# MCU_STM32F4.net
KiCad netlist of a schematic drawn in Altium Designer
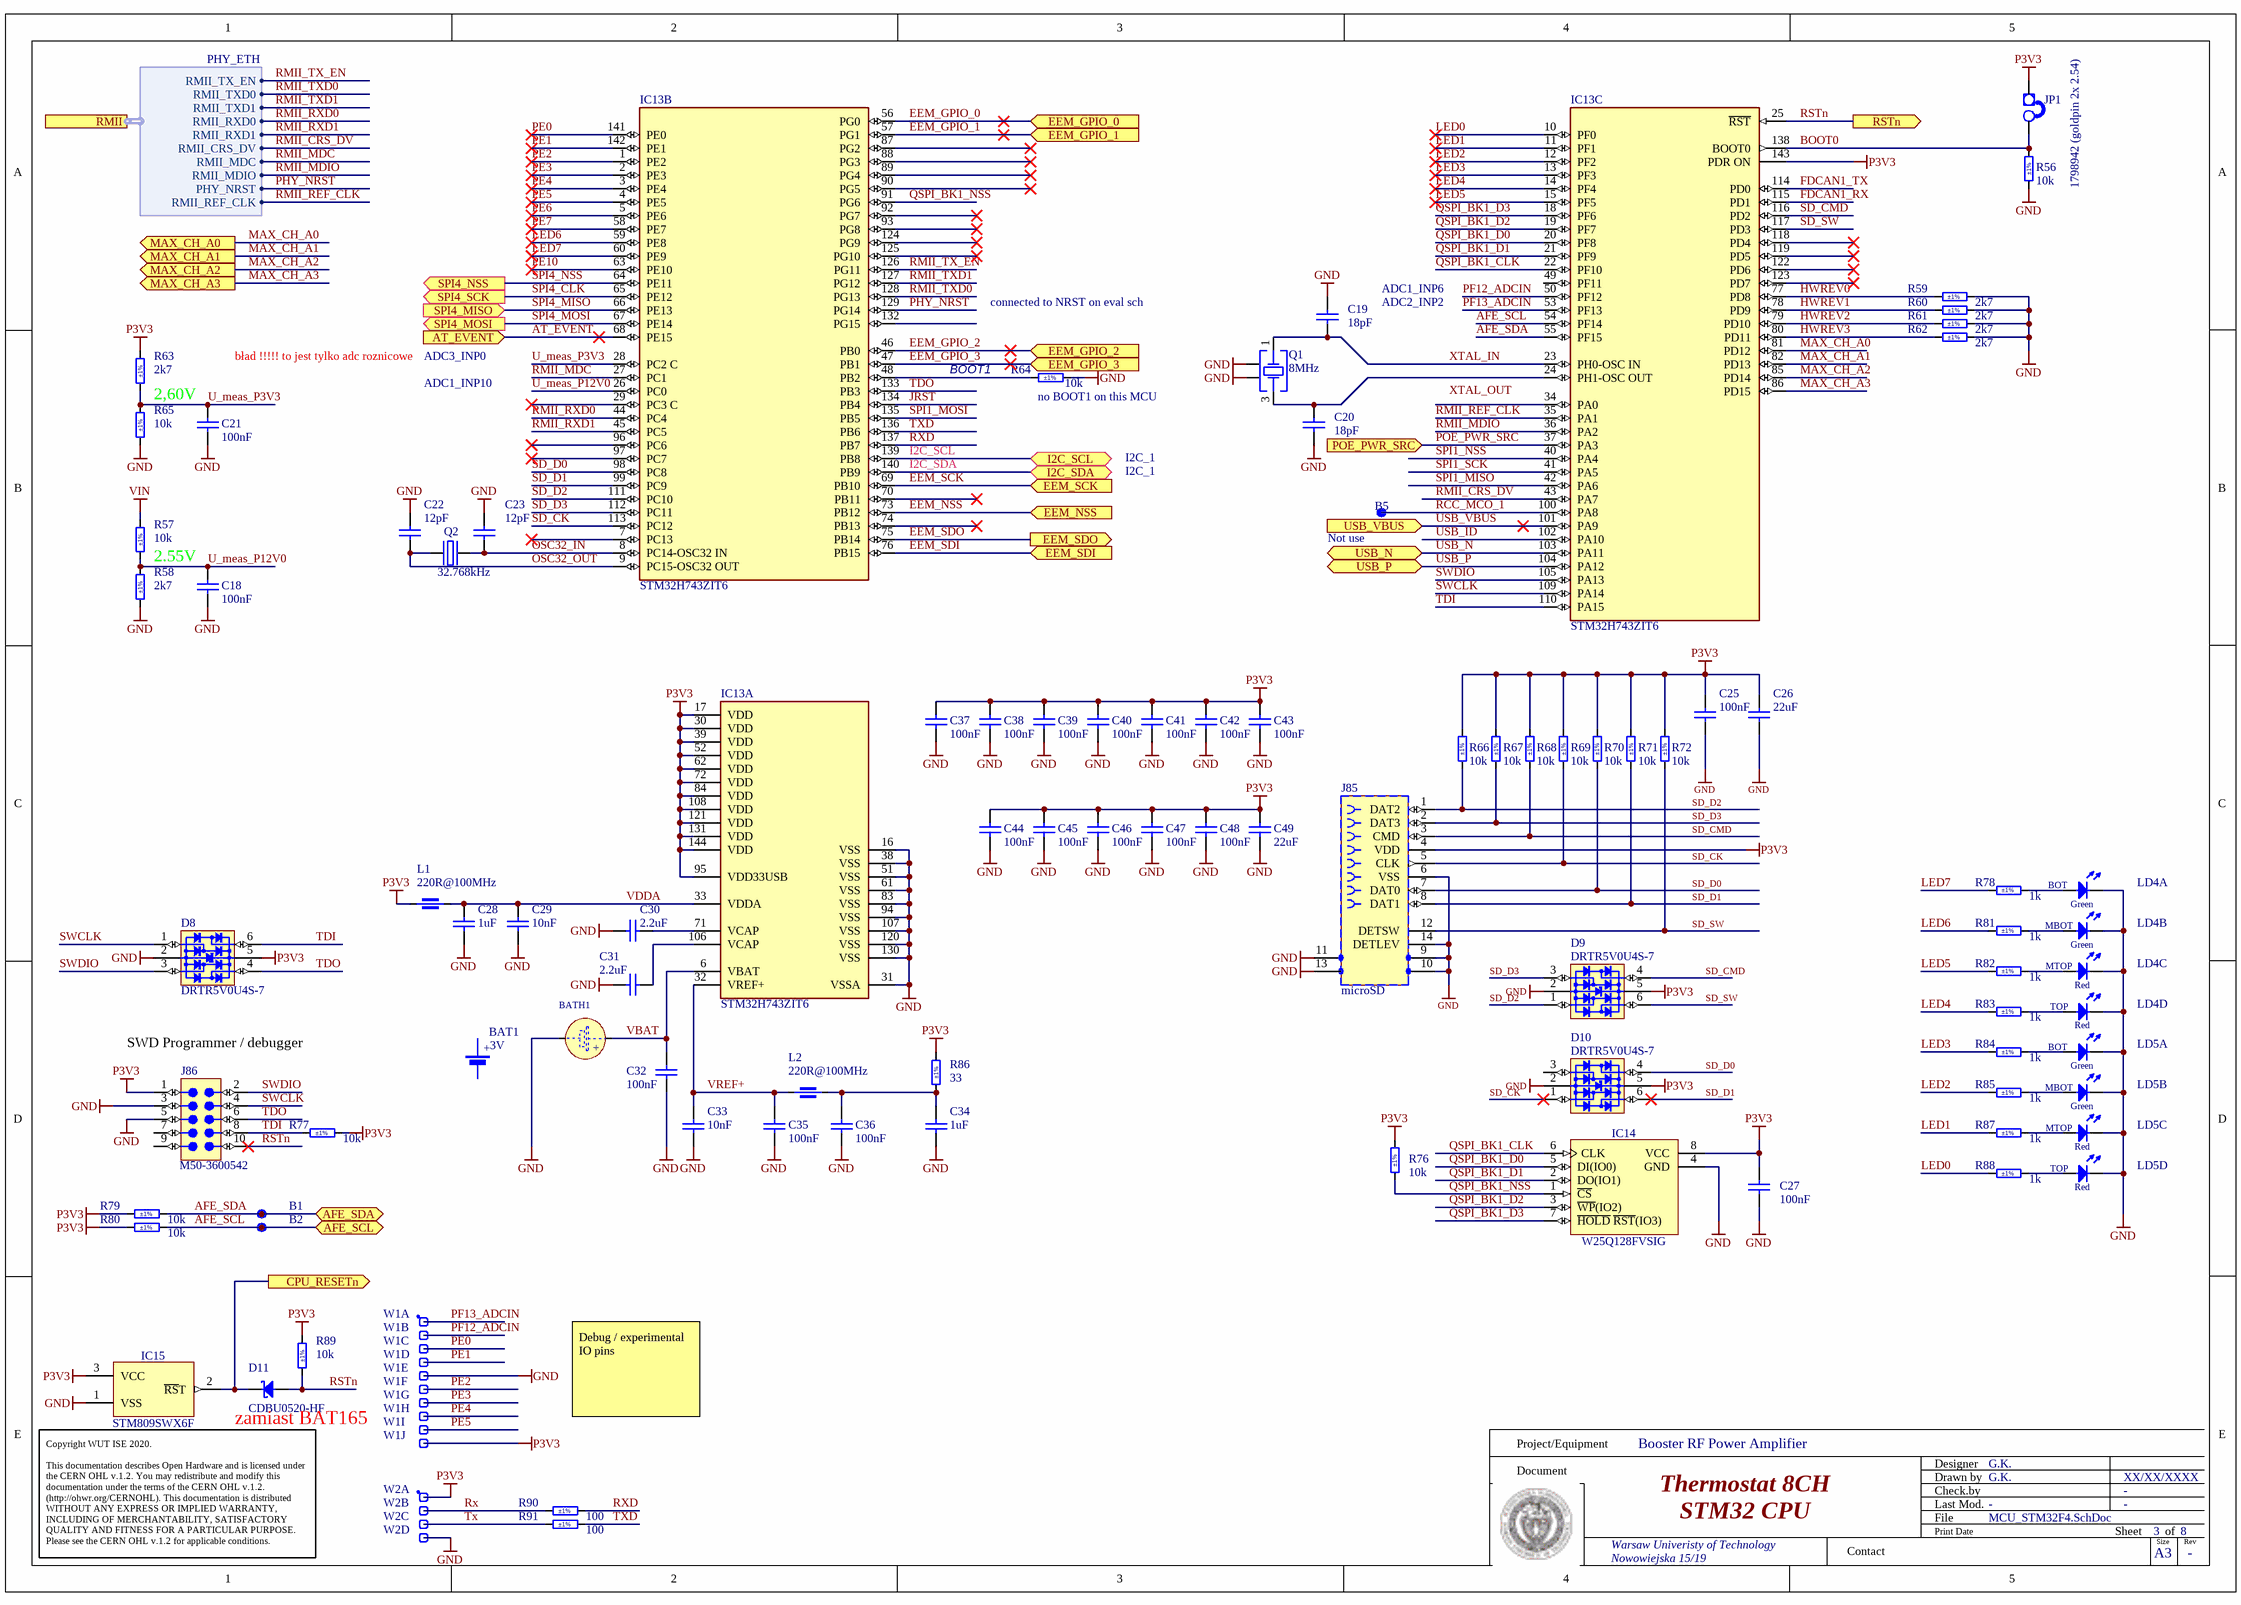
[diagram p0: MCU_STM32F4.SchDoc]

(export (version "E")
  (design (tool "Eeschema 10.0.6"))
  (components
    (comp (ref "B1")
      (value "SMD Pad")
      (footprint "C100")
      (description "Pad")
      (fields (field (name "PART NUMBER") "SMD_PAD_D1MM") (field (name "AUTHOR") "CERN DEM JLC"))
      (libsource (lib "Eletro-mechanical") (part "Single SMD Pad (Round)"))
    )
    (comp (ref "B2")
      (value "SMD Pad")
      (footprint "C100")
      (description "Pad")
      (fields (field (name "PART NUMBER") "SMD_PAD_D1MM") (field (name "AUTHOR") "CERN DEM JLC"))
      (libsource (lib "Eletro-mechanical") (part "Single SMD Pad (Round)"))
    )
    (comp (ref "B5")
      (value "SMD Pad")
      (footprint "C100")
      (description "Through Hole Pad")
      (fields (field (name "PART NUMBER") "SMD_PAD_D1MM") (field (name "AUTHOR") "CERN DEM JLC"))
      (libsource (lib "Eletro-mechanical") (part "Single SMD Pad (Round)"))
    )
    (comp (ref "BAT1")
      (value "3V")
      (footprint "BAT_VARTA_CR1220")
      (description "Battery for use only with Socket Holder")
      (fields
        (field (name "PART NUMBER") "BAT_VARTA_CR1220")
        (field (name "POWER") "35mAh")
        (field (name "AUTHOR") "CERN DEM JLC")
      )
      (libsource (lib "Eletro-mechanical") (part "Battery No Pin"))
    )
    (comp (ref "BATH1")
      (value "~")
      (footprint "BATH_KEYSTONE_3000")
      (description "Battery Holder whit 2 Pin")
      (fields
        (field (name "PART NUMBER") "BATH_KEYSTONE_3000")
        (field (name "MANUFACTURER") "KEYSTONE")
        (field (name "AUTHOR") "CERN DEM JLC")
      )
      (libsource (lib "Eletro-mechanical") (part "Battery Holder 2 Pin"))
    )
    (comp (ref "C18")
      (value "100nF")
      (footprint "CAPC1608X87N")
      (description "Non-polarised capacitor")
      (fields
        (field (name "PART NUMBER") "CC0603_100NF_50V_10%_X7R")
        (field (name "VOLTAGE") "50V")
        (field (name "AUTHOR") "CERN DEM JLC")
      )
      (libsource (lib "Capacitors") (part "Capacitor - non polarized"))
    )
    (comp (ref "C19")
      (value "18pF")
      (footprint "CAPC1608X87N")
      (description "Non-polarised capacitor")
      (fields
        (field (name "PART NUMBER") "CC0603_18PF_50V_5%_NP0")
        (field (name "VOLTAGE") "50V")
        (field (name "AUTHOR") "CERN DEM JLC")
      )
      (libsource (lib "Capacitors") (part "Capacitor - non polarized"))
    )
    (comp (ref "C20")
      (value "18pF")
      (footprint "CAPC1608X87N")
      (description "Non-polarised capacitor")
      (fields
        (field (name "PART NUMBER") "CC0603_18PF_50V_5%_NP0")
        (field (name "VOLTAGE") "50V")
        (field (name "AUTHOR") "CERN DEM JLC")
      )
      (libsource (lib "Capacitors") (part "Capacitor - non polarized"))
    )
    (comp (ref "C21")
      (value "100nF")
      (footprint "CAPC1608X87N")
      (description "Non-polarised capacitor")
      (fields
        (field (name "PART NUMBER") "CC0603_100NF_50V_10%_X7R")
        (field (name "VOLTAGE") "50V")
        (field (name "AUTHOR") "CERN DEM JLC")
      )
      (libsource (lib "Capacitors") (part "Capacitor - non polarized"))
    )
    (comp (ref "C22")
      (value "12pF")
      (footprint "CAPC1608X87N")
      (description "Non-polarised capacitor")
      (fields
        (field (name "PART NUMBER") "CC0603_12PF_50V_5%_NP0")
        (field (name "VOLTAGE") "50V")
        (field (name "AUTHOR") "CERN DEM JLC")
      )
      (libsource (lib "Capacitors") (part "Capacitor - non polarized"))
    )
    (comp (ref "C23")
      (value "12pF")
      (footprint "CAPC1608X87N")
      (description "Non-polarised capacitor")
      (fields
        (field (name "PART NUMBER") "CC0603_12PF_50V_5%_NP0")
        (field (name "VOLTAGE") "50V")
        (field (name "AUTHOR") "CERN DEM JLC")
      )
      (libsource (lib "Capacitors") (part "Capacitor - non polarized"))
    )
    (comp (ref "C25")
      (value "100nF")
      (footprint "CAPC1608X87N")
      (description "Non-polarised capacitor")
      (fields
        (field (name "PART NUMBER") "CC0603_100NF_50V_10%_X7R")
        (field (name "VOLTAGE") "50V")
        (field (name "AUTHOR") "CERN DEM JLC")
      )
      (libsource (lib "Capacitors") (part "Capacitor - non polarized"))
    )
    (comp (ref "C26")
      (value "22uF")
      (footprint "CAPC2012X135N")
      (description "Non-polarised capacitor")
      (fields
        (field (name "PART NUMBER") "CC0805_22UF_16V_10%_X5R")
        (field (name "VOLTAGE") "16V")
        (field (name "AUTHOR") "CERN DEM JLC")
      )
      (libsource (lib "Capacitors") (part "Capacitor - non polarized"))
    )
    (comp (ref "C27")
      (value "100nF")
      (footprint "CAPC1608X87N")
      (description "Non-polarised capacitor")
      (fields
        (field (name "PART NUMBER") "CC0603_100NF_50V_10%_X7R")
        (field (name "VOLTAGE") "50V")
        (field (name "AUTHOR") "CERN DEM JLC")
      )
      (libsource (lib "Capacitors") (part "Capacitor - non polarized"))
    )
    (comp (ref "C28")
      (value "1uF")
      (footprint "CAPC1608X87N")
      (description "Non-polarised capacitor")
      (fields
        (field (name "PART NUMBER") "CC0603_1UF_16V_10%_X7R")
        (field (name "VOLTAGE") "16V")
        (field (name "AUTHOR") "CERN DEM JLC")
      )
      (libsource (lib "Capacitors") (part "Capacitor - non polarized"))
    )
    (comp (ref "C29")
      (value "10nF")
      (footprint "CAPC1608X87N")
      (description "Non-polarised capacitor")
      (fields
        (field (name "PART NUMBER") "CC0603_10NF_50V_10%_X7R")
        (field (name "VOLTAGE") "50V")
        (field (name "AUTHOR") "CERN DEM JLC")
      )
      (libsource (lib "Capacitors") (part "Capacitor - non polarized"))
    )
    (comp (ref "C30")
      (value "2.2uF")
      (footprint "CAPC1608X90N")
      (description "Non-polarised capacitor")
      (fields
        (field (name "PART NUMBER") "CC0603_2.2UF_10V_20%_X7R")
        (field (name "VOLTAGE") "10V")
        (field (name "AUTHOR") "CERN DEM JLC")
      )
      (libsource (lib "Capacitors") (part "Capacitor - non polarized"))
    )
    (comp (ref "C31")
      (value "2.2uF")
      (footprint "CAPC1608X90N")
      (description "Non-polarised capacitor")
      (fields
        (field (name "PART NUMBER") "CC0603_2.2UF_10V_20%_X7R")
        (field (name "VOLTAGE") "10V")
        (field (name "AUTHOR") "CERN DEM JLC")
      )
      (libsource (lib "Capacitors") (part "Capacitor - non polarized"))
    )
    (comp (ref "C32")
      (value "100nF")
      (footprint "CAPC1608X87N")
      (description "Non-polarised capacitor")
      (fields
        (field (name "PART NUMBER") "CC0603_100NF_50V_10%_X7R")
        (field (name "VOLTAGE") "50V")
        (field (name "AUTHOR") "CERN DEM JLC")
      )
      (libsource (lib "Capacitors") (part "Capacitor - non polarized"))
    )
    (comp (ref "C33")
      (value "10nF")
      (footprint "CAPC1608X87N")
      (description "Non-polarised capacitor")
      (fields
        (field (name "PART NUMBER") "CC0603_10NF_50V_10%_X7R")
        (field (name "VOLTAGE") "50V")
        (field (name "AUTHOR") "CERN DEM JLC")
      )
      (libsource (lib "Capacitors") (part "Capacitor - non polarized"))
    )
    (comp (ref "C34")
      (value "1uF")
      (footprint "CAPC1608X87N")
      (description "Non-polarised capacitor")
      (fields
        (field (name "PART NUMBER") "CC0603_1UF_16V_10%_X7R")
        (field (name "VOLTAGE") "16V")
        (field (name "AUTHOR") "CERN DEM JLC")
      )
      (libsource (lib "Capacitors") (part "Capacitor - non polarized"))
    )
    (comp (ref "C35")
      (value "100nF")
      (footprint "CAPC1608X87N")
      (description "Non-polarised capacitor")
      (fields
        (field (name "PART NUMBER") "CC0603_100NF_50V_10%_X7R")
        (field (name "VOLTAGE") "50V")
        (field (name "AUTHOR") "CERN DEM JLC")
      )
      (libsource (lib "Capacitors") (part "Capacitor - non polarized"))
    )
    (comp (ref "C36")
      (value "100nF")
      (footprint "CAPC1608X87N")
      (description "Non-polarised capacitor")
      (fields
        (field (name "PART NUMBER") "CC0603_100NF_50V_10%_X7R")
        (field (name "VOLTAGE") "50V")
        (field (name "AUTHOR") "CERN DEM JLC")
      )
      (libsource (lib "Capacitors") (part "Capacitor - non polarized"))
    )
    (comp (ref "C37")
      (value "100nF")
      (footprint "CAPC1608X87N")
      (description "Non-polarised capacitor")
      (fields
        (field (name "PART NUMBER") "CC0603_100NF_50V_10%_X7R")
        (field (name "VOLTAGE") "50V")
        (field (name "AUTHOR") "CERN DEM JLC")
      )
      (libsource (lib "Capacitors") (part "Capacitor - non polarized"))
    )
    (comp (ref "C38")
      (value "100nF")
      (footprint "CAPC1608X87N")
      (description "Non-polarised capacitor")
      (fields
        (field (name "PART NUMBER") "CC0603_100NF_50V_10%_X7R")
        (field (name "VOLTAGE") "50V")
        (field (name "AUTHOR") "CERN DEM JLC")
      )
      (libsource (lib "Capacitors") (part "Capacitor - non polarized"))
    )
    (comp (ref "C39")
      (value "100nF")
      (footprint "CAPC1608X87N")
      (description "Non-polarised capacitor")
      (fields
        (field (name "PART NUMBER") "CC0603_100NF_50V_10%_X7R")
        (field (name "VOLTAGE") "50V")
        (field (name "AUTHOR") "CERN DEM JLC")
      )
      (libsource (lib "Capacitors") (part "Capacitor - non polarized"))
    )
    (comp (ref "C40")
      (value "100nF")
      (footprint "CAPC1608X87N")
      (description "Non-polarised capacitor")
      (fields
        (field (name "PART NUMBER") "CC0603_100NF_50V_10%_X7R")
        (field (name "VOLTAGE") "50V")
        (field (name "AUTHOR") "CERN DEM JLC")
      )
      (libsource (lib "Capacitors") (part "Capacitor - non polarized"))
    )
    (comp (ref "C41")
      (value "100nF")
      (footprint "CAPC1608X87N")
      (description "Non-polarised capacitor")
      (fields
        (field (name "PART NUMBER") "CC0603_100NF_50V_10%_X7R")
        (field (name "VOLTAGE") "50V")
        (field (name "AUTHOR") "CERN DEM JLC")
      )
      (libsource (lib "Capacitors") (part "Capacitor - non polarized"))
    )
    (comp (ref "C42")
      (value "100nF")
      (footprint "CAPC1608X87N")
      (description "Non-polarised capacitor")
      (fields
        (field (name "PART NUMBER") "CC0603_100NF_50V_10%_X7R")
        (field (name "VOLTAGE") "50V")
        (field (name "AUTHOR") "CERN DEM JLC")
      )
      (libsource (lib "Capacitors") (part "Capacitor - non polarized"))
    )
    (comp (ref "C43")
      (value "100nF")
      (footprint "CAPC1608X87N")
      (description "Non-polarised capacitor")
      (fields
        (field (name "PART NUMBER") "CC0603_100NF_50V_10%_X7R")
        (field (name "VOLTAGE") "50V")
        (field (name "AUTHOR") "CERN DEM JLC")
      )
      (libsource (lib "Capacitors") (part "Capacitor - non polarized"))
    )
    (comp (ref "C44")
      (value "100nF")
      (footprint "CAPC1608X87N")
      (description "Non-polarised capacitor")
      (fields
        (field (name "PART NUMBER") "CC0603_100NF_50V_10%_X7R")
        (field (name "VOLTAGE") "50V")
        (field (name "AUTHOR") "CERN DEM JLC")
      )
      (libsource (lib "Capacitors") (part "Capacitor - non polarized"))
    )
    (comp (ref "C45")
      (value "100nF")
      (footprint "CAPC1608X87N")
      (description "Non-polarised capacitor")
      (fields
        (field (name "PART NUMBER") "CC0603_100NF_50V_10%_X7R")
        (field (name "VOLTAGE") "50V")
        (field (name "AUTHOR") "CERN DEM JLC")
      )
      (libsource (lib "Capacitors") (part "Capacitor - non polarized"))
    )
    (comp (ref "C46")
      (value "100nF")
      (footprint "CAPC1608X87N")
      (description "Non-polarised capacitor")
      (fields
        (field (name "PART NUMBER") "CC0603_100NF_50V_10%_X7R")
        (field (name "VOLTAGE") "50V")
        (field (name "AUTHOR") "CERN DEM JLC")
      )
      (libsource (lib "Capacitors") (part "Capacitor - non polarized"))
    )
    (comp (ref "C47")
      (value "100nF")
      (footprint "CAPC1608X87N")
      (description "Non-polarised capacitor")
      (fields
        (field (name "PART NUMBER") "CC0603_100NF_50V_10%_X7R")
        (field (name "VOLTAGE") "50V")
        (field (name "AUTHOR") "CERN DEM JLC")
      )
      (libsource (lib "Capacitors") (part "Capacitor - non polarized"))
    )
    (comp (ref "C48")
      (value "100nF")
      (footprint "CAPC1608X87N")
      (description "Non-polarised capacitor")
      (fields
        (field (name "PART NUMBER") "CC0603_100NF_50V_10%_X7R")
        (field (name "VOLTAGE") "50V")
        (field (name "AUTHOR") "CERN DEM JLC")
      )
      (libsource (lib "Capacitors") (part "Capacitor - non polarized"))
    )
    (comp (ref "C49")
      (value "22uF")
      (footprint "CAPC2012X135N")
      (description "Non-polarised capacitor")
      (fields
        (field (name "PART NUMBER") "CC0805_22UF_16V_10%_X5R")
        (field (name "VOLTAGE") "16V")
        (field (name "AUTHOR") "CERN DEM JLC")
      )
      (libsource (lib "Capacitors") (part "Capacitor - non polarized"))
    )
    (comp (ref "D8")
      (value "DRTR5V0U4S-7")
      (footprint "SOT65P210X110-6N")
      (description "Integrated Quad Ultra-Low Capacitance ESD Protection")
      (fields (field (name "MANUFACTURER") "DIODES") (field (name "AUTHOR") "GK"))
      (libsource (lib "Diodes") (part "D_TVS_DRTR5V0U4S-7"))
    )
    (comp (ref "D9")
      (value "DRTR5V0U4S-7")
      (footprint "SOT65P210X110-6N")
      (description "Integrated Quad Ultra-Low Capacitance ESD Protection")
      (fields (field (name "MANUFACTURER") "DIODES") (field (name "AUTHOR") "GK"))
      (libsource (lib "Diodes") (part "D_TVS_DRTR5V0U4S-7"))
    )
    (comp (ref "D10")
      (value "DRTR5V0U4S-7")
      (footprint "SOT65P210X110-6N")
      (description "Integrated Quad Ultra-Low Capacitance ESD Protection")
      (fields (field (name "MANUFACTURER") "DIODES") (field (name "AUTHOR") "GK"))
      (libsource (lib "Diodes") (part "D_TVS_DRTR5V0U4S-7"))
    )
    (comp (ref "D11")
      (value "CDBU0520-HF")
      (footprint "SOD-523F")
      (description "Schottky Diode")
      (fields
        (field (name "VOLTAGE") "20V")
        (field (name "POWER") "500mA")
        (field (name "AUTHOR") "CERN DEM HF")
      )
      (libsource (lib "ICs And Semiconductors") (part "Diode Schottky"))
    )
    (comp (ref "IC13")
      (value "STM32H743ZIT6")
      (footprint "FP-LQFP144-1A-MFG")
      (description "IC MCU 32BIT 2MB FLASH 144LQFP")
      (fields
        (field (name "MANUFACTURER") "STMicroelectronics")
        (field (name "OCTOPART") "https://octopart.com/stm32h743zit6-stmicroelectronics-76372529")
      )
      (libsource (lib "Altium Content Vault") (part "4977c5c7f8d170b58ef15f889e64ba1"))
    )
    (comp (ref "IC14")
      (value "W25Q128FVSIG")
      (footprint "SOIC127P790X216-8N")
      (description "128M-bit Serial Flash Memory with uniform 4KB sectors and Dual/Quad SPI and QPI")
      (fields (field (name "MANUFACTURER") "WINBOND") (field (name "AUTHOR") "CERN DEM MR"))
      (libsource (lib "ICs And Semiconductors") (part "W25Q128FVSIG"))
    )
    (comp (ref "IC15")
      (value "STM809SWX6F")
      (footprint "SOT95P237X112-3N")
      (description "3-Pin Microprocessor Reset Circuit")
      (fields (field (name "MANUFACTURER") "ST MICROELECTRONICS") (field (name "AUTHOR") "CERN DEM JMW"))
      (libsource (lib "ICs And Semiconductors") (part "STM809SWX6F"))
    )
    (comp (ref "J85")
      (value "microSD")
      (footprint "MOLEX_502570-0893")
      (description "Connector MicroSD 8 Pin")
      (fields
        (field (name "PART NUMBER") "MOLEX_502570-0893")
        (field (name "MANUFACTURER") "MOLEX")
        (field (name "AUTHOR") "CERN DEM JLC")
      )
      (libsource (lib "Connectors") (part "MOLEX_502570-0893"))
    )
    (comp (ref "J86")
      (value "Header 10")
      (footprint "HARWIN_M50-3600542")
      (description "10 Contacts - Pitch 1.27mm - Dual Row SMT Vertical Pin Header (Post Lead = 3mm, Insulator 1mm)")
      (fields
        (field (name "PART NUMBER") "HARWIN_M50-3600542")
        (field (name "MANUFACTURER") "HARWIN")
        (field (name "MANUFACTURER PART NUMBER") "M50-3600542")
        (field (name "AUTHOR") "GK")
      )
      (libsource (lib "PT1000_16CH") (part "CON_2x10 1.27 SMT_male_HARWIN"))
    )
    (comp (ref "JP1")
      (value "1798942 (goldpin 2x 2.54)")
      (footprint "jump")
      (description "Jumper")
      (libsource (lib "PT1000_16CH") (part "JUMPER"))
    )
    (comp (ref "L1")
      (value "220R@100MHz")
      (footprint "INDC1608X95N")
      (fields
        (field (name "PART NUMBER") "IND0603_MURATA_BLM18SG221TN1")
        (field (name "POWER") "2.5A")
        (field (name "TOLERANCE") "±25%")
        (field (name "AUTHOR") "CERN DEM MR")
      )
      (libsource (lib "Inductors & Transformers") (part "Ferrite Bead"))
    )
    (comp (ref "L2")
      (value "220R@100MHz")
      (footprint "INDC1608X95N")
      (fields
        (field (name "PART NUMBER") "IND0603_MURATA_BLM18SG221TN1")
        (field (name "POWER") "2.5A")
        (field (name "TOLERANCE") "±25%")
        (field (name "AUTHOR") "CERN DEM MR")
      )
      (libsource (lib "Inductors & Transformers") (part "Ferrite Bead"))
    )
    (comp (ref "LD4")
      (value "Green/Green/HeRed/HeRed")
      (footprint "LED_BIVAR_H485CHHGGDL")
      (description "LED x4 G-1C2A-BOT_G-3C4A_H-5C6A_H-7C8A-TOP")
      (fields
        (field (name "PART NUMBER") "LED_BIVAR_H485CHHGGDL")
        (field (name "MANUFACTURER") "BIVAR")
        (field (name "AUTHOR") "CERN DEM BC")
      )
      (libsource (lib "ICs And Semiconductors") (part "LED x4 G-1C2A-BOT_G-3C4A_H-5C6A_H-7C8A-TOP"))
    )
    (comp (ref "LD5")
      (value "Green/Green/HeRed/HeRed")
      (footprint "LED_BIVAR_H485CHHGGDL")
      (description "LED x4 G-1C2A-BOT_G-3C4A_H-5C6A_H-7C8A-TOP")
      (fields
        (field (name "PART NUMBER") "LED_BIVAR_H485CHHGGDL")
        (field (name "MANUFACTURER") "BIVAR")
        (field (name "AUTHOR") "CERN DEM BC")
      )
      (libsource (lib "ICs And Semiconductors") (part "LED x4 G-1C2A-BOT_G-3C4A_H-5C6A_H-7C8A-TOP"))
    )
    (comp (ref "Q1")
      (value "8MHz")
      (footprint "WE-XTAL_CFPX-180")
      (description "WE-XTAL Quartz Crystal, SMT, CFPX-180, 8MHz, +/-30ppm")
      (fields
        (field (name "MANUFACTURER PART NUMBER") "830108313809")
        (field (name "MANUFACTURER") "Wurth Elektronik")
        (field (name "FREQUENCY") "8MHz")
      )
      (libsource (lib "Altium_WE-XTAL (rev22a)") (part "830108313809"))
    )
    (comp (ref "Q2")
      (value "32.768kHz")
      (footprint "XTAL_ABRACON_ABS06")
      (description "Quartz Crystal")
      (fields
        (field (name "PART NUMBER") "XTAL_32.768KHZ_ABRACON_ABS06-32.768KHZ-9")
        (field (name "MANUFACTURER") "ABRACON")
        (field (name "AUTHOR") "CERN DEM JMW")
      )
      (libsource (lib "ICs And Semiconductors") (part "Quartz Crystal"))
    )
    (comp (ref "R56")
      (value "10k")
      (footprint "RESC1608X55N")
      (description "Resistor - 1%")
      (fields
        (field (name "TOLERANCE") "±1%")
        (field (name "PART NUMBER") "R0603_10K_1%_0.1W_100PPM")
        (field (name "POWER") "0.1W")
        (field (name "AUTHOR") "CERN DEM JLC")
      )
      (libsource (lib "Resistors") (part "Resistor - 1%"))
    )
    (comp (ref "R57")
      (value "10k")
      (footprint "RESC1608X55N")
      (description "Resistor - 1%")
      (fields
        (field (name "TOLERANCE") "±1%")
        (field (name "PART NUMBER") "R0603_10K_1%_0.1W_100PPM")
        (field (name "POWER") "0.1W")
        (field (name "AUTHOR") "CERN DEM JLC")
      )
      (libsource (lib "Resistors") (part "Resistor - 1%"))
    )
    (comp (ref "R58")
      (value "2k7")
      (footprint "RESC1608X55N")
      (description "Resistor - 1%")
      (fields
        (field (name "TOLERANCE") "±1%")
        (field (name "PART NUMBER") "R0603_2K7_1%_0.1W_100PPM")
        (field (name "POWER") "0.1W")
        (field (name "AUTHOR") "CERN DEM JLC")
      )
      (libsource (lib "Resistors") (part "Resistor - 1%"))
    )
    (comp (ref "R59")
      (value "2k7")
      (footprint "RESC1608X55N")
      (description "Resistor - 1%")
      (fields
        (field (name "TOLERANCE") "±1%")
        (field (name "PART NUMBER") "R0603_2K7_1%_0.1W_100PPM")
        (field (name "POWER") "0.1W")
        (field (name "AUTHOR") "CERN DEM JLC")
      )
      (libsource (lib "Resistors") (part "Resistor - 1%"))
    )
    (comp (ref "R60")
      (value "2k7")
      (footprint "RESC1608X55N")
      (description "Resistor - 1%")
      (fields
        (field (name "TOLERANCE") "±1%")
        (field (name "PART NUMBER") "R0603_2K7_1%_0.1W_100PPM")
        (field (name "POWER") "0.1W")
        (field (name "AUTHOR") "CERN DEM JLC")
      )
      (libsource (lib "Resistors") (part "Resistor - 1%"))
    )
    (comp (ref "R61")
      (value "2k7")
      (footprint "RESC1608X55N")
      (description "Resistor - 1%")
      (fields
        (field (name "TOLERANCE") "±1%")
        (field (name "PART NUMBER") "R0603_2K7_1%_0.1W_100PPM")
        (field (name "POWER") "0.1W")
        (field (name "AUTHOR") "CERN DEM JLC")
      )
      (libsource (lib "Resistors") (part "Resistor - 1%"))
    )
    (comp (ref "R62")
      (value "2k7")
      (footprint "RESC1608X55N")
      (description "Resistor - 1%")
      (fields
        (field (name "TOLERANCE") "±1%")
        (field (name "PART NUMBER") "R0603_2K7_1%_0.1W_100PPM")
        (field (name "POWER") "0.1W")
        (field (name "AUTHOR") "CERN DEM JLC")
      )
      (libsource (lib "Resistors") (part "Resistor - 1%"))
    )
    (comp (ref "R63")
      (value "2k7")
      (footprint "RESC1608X55N")
      (description "Resistor - 1%")
      (fields
        (field (name "TOLERANCE") "±1%")
        (field (name "PART NUMBER") "R0603_2K7_1%_0.1W_100PPM")
        (field (name "POWER") "0.1W")
        (field (name "AUTHOR") "CERN DEM JLC")
      )
      (libsource (lib "Resistors") (part "Resistor - 1%"))
    )
    (comp (ref "R64")
      (value "10k")
      (footprint "RESC1608X55N")
      (description "Resistor - 1%")
      (fields
        (field (name "TOLERANCE") "±1%")
        (field (name "PART NUMBER") "R0603_10K_1%_0.1W_100PPM")
        (field (name "POWER") "0.1W")
        (field (name "AUTHOR") "CERN DEM JLC")
      )
      (libsource (lib "Resistors") (part "Resistor - 1%"))
    )
    (comp (ref "R65")
      (value "10k")
      (footprint "RESC1608X55N")
      (description "Resistor - 1%")
      (fields
        (field (name "TOLERANCE") "±1%")
        (field (name "PART NUMBER") "R0603_10K_1%_0.1W_100PPM")
        (field (name "POWER") "0.1W")
        (field (name "AUTHOR") "CERN DEM JLC")
      )
      (libsource (lib "Resistors") (part "Resistor - 1%"))
    )
    (comp (ref "R66")
      (value "10k")
      (footprint "RESC1608X55N")
      (description "Resistor - 1%")
      (fields
        (field (name "TOLERANCE") "±1%")
        (field (name "PART NUMBER") "R0603_10K_1%_0.1W_100PPM")
        (field (name "POWER") "0.1W")
        (field (name "AUTHOR") "CERN DEM JLC")
      )
      (libsource (lib "Resistors") (part "Resistor - 1%"))
    )
    (comp (ref "R67")
      (value "10k")
      (footprint "RESC1608X55N")
      (description "Resistor - 1%")
      (fields
        (field (name "TOLERANCE") "±1%")
        (field (name "PART NUMBER") "R0603_10K_1%_0.1W_100PPM")
        (field (name "POWER") "0.1W")
        (field (name "AUTHOR") "CERN DEM JLC")
      )
      (libsource (lib "Resistors") (part "Resistor - 1%"))
    )
    (comp (ref "R68")
      (value "10k")
      (footprint "RESC1608X55N")
      (description "Resistor - 1%")
      (fields
        (field (name "TOLERANCE") "±1%")
        (field (name "PART NUMBER") "R0603_10K_1%_0.1W_100PPM")
        (field (name "POWER") "0.1W")
        (field (name "AUTHOR") "CERN DEM JLC")
      )
      (libsource (lib "Resistors") (part "Resistor - 1%"))
    )
    (comp (ref "R69")
      (value "10k")
      (footprint "RESC1608X55N")
      (description "Resistor - 1%")
      (fields
        (field (name "TOLERANCE") "±1%")
        (field (name "PART NUMBER") "R0603_10K_1%_0.1W_100PPM")
        (field (name "POWER") "0.1W")
        (field (name "AUTHOR") "CERN DEM JLC")
      )
      (libsource (lib "Resistors") (part "Resistor - 1%"))
    )
    (comp (ref "R70")
      (value "10k")
      (footprint "RESC1608X55N")
      (description "Resistor - 1%")
      (fields
        (field (name "TOLERANCE") "±1%")
        (field (name "PART NUMBER") "R0603_10K_1%_0.1W_100PPM")
        (field (name "POWER") "0.1W")
        (field (name "AUTHOR") "CERN DEM JLC")
      )
      (libsource (lib "Resistors") (part "Resistor - 1%"))
    )
    (comp (ref "R71")
      (value "10k")
      (footprint "RESC1608X55N")
      (description "Resistor - 1%")
      (fields
        (field (name "TOLERANCE") "±1%")
        (field (name "PART NUMBER") "R0603_10K_1%_0.1W_100PPM")
        (field (name "POWER") "0.1W")
        (field (name "AUTHOR") "CERN DEM JLC")
      )
      (libsource (lib "Resistors") (part "Resistor - 1%"))
    )
    (comp (ref "R72")
      (value "10k")
      (footprint "RESC1608X55N")
      (description "Resistor - 1%")
      (fields
        (field (name "TOLERANCE") "±1%")
        (field (name "PART NUMBER") "R0603_10K_1%_0.1W_100PPM")
        (field (name "POWER") "0.1W")
        (field (name "AUTHOR") "CERN DEM JLC")
      )
      (libsource (lib "Resistors") (part "Resistor - 1%"))
    )
    (comp (ref "R76")
      (value "10k")
      (footprint "RESC1608X55N")
      (description "Resistor - 1%")
      (fields
        (field (name "TOLERANCE") "±1%")
        (field (name "PART NUMBER") "R0603_10K_1%_0.1W_100PPM")
        (field (name "POWER") "0.1W")
        (field (name "AUTHOR") "CERN DEM JLC")
      )
      (libsource (lib "Resistors") (part "Resistor - 1%"))
    )
    (comp (ref "R77")
      (value "10k")
      (footprint "RESC1608X55N")
      (description "Resistor - 1%")
      (fields
        (field (name "TOLERANCE") "±1%")
        (field (name "PART NUMBER") "R0603_10K_1%_0.1W_100PPM")
        (field (name "POWER") "0.1W")
        (field (name "AUTHOR") "CERN DEM JLC")
      )
      (libsource (lib "Resistors") (part "Resistor - 1%"))
    )
    (comp (ref "R78")
      (value "1k")
      (footprint "RESC1608X55N")
      (description "Resistor - 1%")
      (fields
        (field (name "TOLERANCE") "±1%")
        (field (name "PART NUMBER") "R0603_1K_1%_0.1W_100PPM")
        (field (name "POWER") "0.1W")
        (field (name "AUTHOR") "CERN DEM JLC")
      )
      (libsource (lib "Resistors") (part "Resistor - 1%"))
    )
    (comp (ref "R79")
      (value "10k")
      (footprint "RESC1608X55N")
      (description "Resistor - 1%")
      (fields
        (field (name "TOLERANCE") "±1%")
        (field (name "PART NUMBER") "R0603_10K_1%_0.1W_100PPM")
        (field (name "POWER") "0.1W")
        (field (name "AUTHOR") "CERN DEM JLC")
      )
      (libsource (lib "Resistors") (part "Resistor - 1%"))
    )
    (comp (ref "R80")
      (value "10k")
      (footprint "RESC1608X55N")
      (description "Resistor - 1%")
      (fields
        (field (name "TOLERANCE") "±1%")
        (field (name "PART NUMBER") "R0603_10K_1%_0.1W_100PPM")
        (field (name "POWER") "0.1W")
        (field (name "AUTHOR") "CERN DEM JLC")
      )
      (libsource (lib "Resistors") (part "Resistor - 1%"))
    )
    (comp (ref "R81")
      (value "1k")
      (footprint "RESC1608X55N")
      (description "Resistor - 1%")
      (fields
        (field (name "TOLERANCE") "±1%")
        (field (name "PART NUMBER") "R0603_1K_1%_0.1W_100PPM")
        (field (name "POWER") "0.1W")
        (field (name "AUTHOR") "CERN DEM JLC")
      )
      (libsource (lib "Resistors") (part "Resistor - 1%"))
    )
    (comp (ref "R82")
      (value "1k")
      (footprint "RESC1608X55N")
      (description "Resistor - 1%")
      (fields
        (field (name "TOLERANCE") "±1%")
        (field (name "PART NUMBER") "R0603_1K_1%_0.1W_100PPM")
        (field (name "POWER") "0.1W")
        (field (name "AUTHOR") "CERN DEM JLC")
      )
      (libsource (lib "Resistors") (part "Resistor - 1%"))
    )
    (comp (ref "R83")
      (value "1k")
      (footprint "RESC1608X55N")
      (description "Resistor - 1%")
      (fields
        (field (name "TOLERANCE") "±1%")
        (field (name "PART NUMBER") "R0603_1K_1%_0.1W_100PPM")
        (field (name "POWER") "0.1W")
        (field (name "AUTHOR") "CERN DEM JLC")
      )
      (libsource (lib "Resistors") (part "Resistor - 1%"))
    )
    (comp (ref "R84")
      (value "1k")
      (footprint "RESC1608X55N")
      (description "Resistor - 1%")
      (fields
        (field (name "TOLERANCE") "±1%")
        (field (name "PART NUMBER") "R0603_1K_1%_0.1W_100PPM")
        (field (name "POWER") "0.1W")
        (field (name "AUTHOR") "CERN DEM JLC")
      )
      (libsource (lib "Resistors") (part "Resistor - 1%"))
    )
    (comp (ref "R85")
      (value "1k")
      (footprint "RESC1608X55N")
      (description "Resistor - 1%")
      (fields
        (field (name "TOLERANCE") "±1%")
        (field (name "PART NUMBER") "R0603_1K_1%_0.1W_100PPM")
        (field (name "POWER") "0.1W")
        (field (name "AUTHOR") "CERN DEM JLC")
      )
      (libsource (lib "Resistors") (part "Resistor - 1%"))
    )
    (comp (ref "R86")
      (value "33")
      (footprint "RESC1608X55N")
      (description "Resistor - 1%")
      (fields
        (field (name "TOLERANCE") "±1%")
        (field (name "PART NUMBER") "R0603_33R_1%_0.1W_100PPM")
        (field (name "POWER") "0.1W")
        (field (name "AUTHOR") "CERN DEM JLC")
      )
      (libsource (lib "Resistors") (part "Resistor - 1%"))
    )
    (comp (ref "R87")
      (value "1k")
      (footprint "RESC1608X55N")
      (description "Resistor - 1%")
      (fields
        (field (name "TOLERANCE") "±1%")
        (field (name "PART NUMBER") "R0603_1K_1%_0.1W_100PPM")
        (field (name "POWER") "0.1W")
        (field (name "AUTHOR") "CERN DEM JLC")
      )
      (libsource (lib "Resistors") (part "Resistor - 1%"))
    )
    (comp (ref "R88")
      (value "1k")
      (footprint "RESC1608X55N")
      (description "Resistor - 1%")
      (fields
        (field (name "TOLERANCE") "±1%")
        (field (name "PART NUMBER") "R0603_1K_1%_0.1W_100PPM")
        (field (name "POWER") "0.1W")
        (field (name "AUTHOR") "CERN DEM JLC")
      )
      (libsource (lib "Resistors") (part "Resistor - 1%"))
    )
    (comp (ref "R89")
      (value "10k")
      (footprint "RESC1608X55N")
      (description "Resistor - 1%")
      (fields
        (field (name "TOLERANCE") "±1%")
        (field (name "PART NUMBER") "R0603_10K_1%_0.1W_100PPM")
        (field (name "POWER") "0.1W")
        (field (name "AUTHOR") "CERN DEM JLC")
      )
      (libsource (lib "Resistors") (part "Resistor - 1%"))
    )
    (comp (ref "R90")
      (value "100")
      (footprint "RESC1608X55N")
      (description "Resistor - 1%")
      (fields
        (field (name "TOLERANCE") "±1%")
        (field (name "PART NUMBER") "R0603_100R_1%_0.1W_100PPM")
        (field (name "POWER") "0.1W")
        (field (name "AUTHOR") "CERN DEM JLC")
      )
      (libsource (lib "Resistors") (part "Resistor - 1%"))
    )
    (comp (ref "R91")
      (value "100")
      (footprint "RESC1608X55N")
      (description "Resistor - 1%")
      (fields
        (field (name "TOLERANCE") "±1%")
        (field (name "PART NUMBER") "R0603_100R_1%_0.1W_100PPM")
        (field (name "POWER") "0.1W")
        (field (name "AUTHOR") "CERN DEM JLC")
      )
      (libsource (lib "Resistors") (part "Resistor - 1%"))
    )
    (comp (ref "W1")
      (value "Header 10")
      (footprint "SAMTEC_MTLW-110-07-L-S-250")
      (description "10 Mini Wire-Wrap Contact Strip Header")
      (fields
        (field (name "PART NUMBER") "SAMTEC_MTLW-110-07-L-S-250")
        (field (name "MANUFACTURER") "SAMTEC")
        (field (name "AUTHOR") "CERN DEM JLC")
      )
      (libsource (lib "Connectors") (part "Wire-Wrap Contact x10"))
    )
    (comp (ref "W2")
      (value "Header 4")
      (footprint "SAMTEC_HTSW-104-23-L-S")
      (description "4 Mini Wire-Wrap Contact Strip Header")
      (fields
        (field (name "PART NUMBER") "SAMTEC_HTSW-104-23-L-S")
        (field (name "MANUFACTURER") "SAMTEC")
        (field (name "AUTHOR") "CERN DEM JLC")
      )
      (libsource (lib "Connectors") (part "Wire-Wrap Contact x4"))
    )
  )
  (nets
    (net (code "2") (name "/AFE_SCL") (class "Default")
      (node (ref "B2") (pin "1") (pinfunction "1_1") (pintype "bidirectional"))
      (node (ref "IC13") (pin "54") (pinfunction "PF14_54") (pintype "bidirectional"))
      (node (ref "R80") (pin "2") (pinfunction "2_2") (pintype "passive"))
    )
    (net (code "3") (name "/AFE_SDA") (class "Default")
      (node (ref "B1") (pin "1") (pinfunction "1_1") (pintype "bidirectional"))
      (node (ref "IC13") (pin "55") (pinfunction "PF15_55") (pintype "bidirectional"))
      (node (ref "R79") (pin "2") (pinfunction "2_2") (pintype "passive"))
    )
    (net (code "4") (name "/AT_EVENT") (class "Default")
      (node (ref "IC13") (pin "68") (pinfunction "PE15_68") (pintype "bidirectional"))
    )
    (net (code "5") (name "/BOOT0") (class "Default")
      (node (ref "IC13") (pin "138") (pinfunction "BOOT0_138") (pintype "output"))
      (node (ref "JP1") (pin "2") (pinfunction "E2_2") (pintype "passive"))
      (node (ref "R56") (pin "2") (pinfunction "2_2") (pintype "passive"))
    )
    (net (code "6") (name "/CPU_RESETn") (class "Default")
      (node (ref "D11") (pin "1") (pinfunction "C_1") (pintype "passive"))
      (node (ref "IC15") (pin "2") (pinfunction "~{RS}T_2") (pintype "output"))
    )
    (net (code "7") (name "/EEM_GPIO_0") (class "Default")
      (node (ref "IC13") (pin "56") (pinfunction "PG0_56") (pintype "bidirectional"))
    )
    (net (code "8") (name "/EEM_GPIO_1") (class "Default")
      (node (ref "IC13") (pin "57") (pinfunction "PG1_57") (pintype "bidirectional"))
    )
    (net (code "9") (name "/EEM_GPIO_2") (class "Default")
      (node (ref "IC13") (pin "46") (pinfunction "PB0_46") (pintype "bidirectional"))
    )
    (net (code "10") (name "/EEM_GPIO_3") (class "Default")
      (node (ref "IC13") (pin "47") (pinfunction "PB1_47") (pintype "bidirectional"))
    )
    (net (code "11") (name "/EEM_NSS") (class "Default")
      (node (ref "IC13") (pin "73") (pinfunction "PB12_73") (pintype "bidirectional"))
    )
    (net (code "12") (name "/EEM_SCK") (class "Default")
      (node (ref "IC13") (pin "69") (pinfunction "PB10_69") (pintype "bidirectional"))
    )
    (net (code "13") (name "/EEM_SDI") (class "Default")
      (node (ref "IC13") (pin "76") (pinfunction "PB15_76") (pintype "bidirectional"))
    )
    (net (code "14") (name "/EEM_SDO") (class "Default")
      (node (ref "IC13") (pin "75") (pinfunction "PB14_75") (pintype "bidirectional"))
    )
    (net (code "15") (name "/FDCAN1_RX") (class "Default")
      (node (ref "IC13") (pin "115") (pinfunction "PD1_115") (pintype "bidirectional"))
    )
    (net (code "16") (name "/FDCAN1_TX") (class "Default")
      (node (ref "IC13") (pin "114") (pinfunction "PD0_114") (pintype "bidirectional"))
    )
    (net (code "17") (name "/HWREV0") (class "Default")
      (node (ref "IC13") (pin "77") (pinfunction "PD8_77") (pintype "bidirectional"))
      (node (ref "R59") (pin "1") (pinfunction "1_1") (pintype "passive"))
    )
    (net (code "18") (name "/HWREV1") (class "Default")
      (node (ref "IC13") (pin "78") (pinfunction "PD9_78") (pintype "bidirectional"))
      (node (ref "R60") (pin "1") (pinfunction "1_1") (pintype "passive"))
    )
    (net (code "19") (name "/HWREV2") (class "Default")
      (node (ref "IC13") (pin "79") (pinfunction "PD10_79") (pintype "bidirectional"))
      (node (ref "R61") (pin "1") (pinfunction "1_1") (pintype "passive"))
    )
    (net (code "20") (name "/HWREV3") (class "Default")
      (node (ref "IC13") (pin "80") (pinfunction "PD11_80") (pintype "bidirectional"))
      (node (ref "R62") (pin "1") (pinfunction "1_1") (pintype "passive"))
    )
    (net (code "21") (name "/I2C_SCL") (class "Default")
      (node (ref "IC13") (pin "139") (pinfunction "PB8_139") (pintype "bidirectional"))
    )
    (net (code "22") (name "/I2C_SDA") (class "Default")
      (node (ref "IC13") (pin "140") (pinfunction "PB9_140") (pintype "bidirectional"))
    )
    (net (code "23") (name "/JRST") (class "Default")
      (node (ref "IC13") (pin "134") (pinfunction "PB4_134") (pintype "bidirectional"))
    )
    (net (code "24") (name "/LED0") (class "Default")
      (node (ref "IC13") (pin "10") (pinfunction "PF0_10") (pintype "bidirectional"))
      (node (ref "R88") (pin "1") (pinfunction "1_1") (pintype "passive"))
    )
    (net (code "25") (name "/LED1") (class "Default")
      (node (ref "IC13") (pin "11") (pinfunction "PF1_11") (pintype "bidirectional"))
      (node (ref "R87") (pin "1") (pinfunction "1_1") (pintype "passive"))
    )
    (net (code "26") (name "/LED2") (class "Default")
      (node (ref "IC13") (pin "12") (pinfunction "PF2_12") (pintype "bidirectional"))
      (node (ref "R85") (pin "1") (pinfunction "1_1") (pintype "passive"))
    )
    (net (code "27") (name "/LED3") (class "Default")
      (node (ref "IC13") (pin "13") (pinfunction "PF3_13") (pintype "bidirectional"))
      (node (ref "R84") (pin "1") (pinfunction "1_1") (pintype "passive"))
    )
    (net (code "28") (name "/LED4") (class "Default")
      (node (ref "IC13") (pin "14") (pinfunction "PF4_14") (pintype "bidirectional"))
      (node (ref "R83") (pin "1") (pinfunction "1_1") (pintype "passive"))
    )
    (net (code "29") (name "/LED5") (class "Default")
      (node (ref "IC13") (pin "15") (pinfunction "PF5_15") (pintype "bidirectional"))
      (node (ref "R82") (pin "1") (pinfunction "1_1") (pintype "passive"))
    )
    (net (code "30") (name "/LED6") (class "Default")
      (node (ref "IC13") (pin "59") (pinfunction "PE8_59") (pintype "bidirectional"))
      (node (ref "R81") (pin "1") (pinfunction "1_1") (pintype "passive"))
    )
    (net (code "31") (name "/LED7") (class "Default")
      (node (ref "IC13") (pin "60") (pinfunction "PE9_60") (pintype "bidirectional"))
      (node (ref "R78") (pin "1") (pinfunction "1_1") (pintype "passive"))
    )
    (net (code "32") (name "/MAX_CH_A0") (class "Default")
      (node (ref "IC13") (pin "81") (pinfunction "PD12_81") (pintype "bidirectional"))
    )
    (net (code "33") (name "/MAX_CH_A1") (class "Default")
      (node (ref "IC13") (pin "82") (pinfunction "PD13_82") (pintype "bidirectional"))
    )
    (net (code "34") (name "/MAX_CH_A2") (class "Default")
      (node (ref "IC13") (pin "85") (pinfunction "PD14_85") (pintype "bidirectional"))
    )
    (net (code "35") (name "/MAX_CH_A3") (class "Default")
      (node (ref "IC13") (pin "86") (pinfunction "PD15_86") (pintype "bidirectional"))
    )
    (net (code "36") (name "/OSC32_IN") (class "Default")
      (node (ref "C23") (pin "1") (pinfunction "1_1") (pintype "passive"))
      (node (ref "IC13") (pin "8") (pinfunction "PC14-OSC32_IN_8") (pintype "bidirectional"))
      (node (ref "Q2") (pin "2") (pinfunction "OSC2_2") (pintype "passive"))
    )
    (net (code "37") (name "/OSC32_OUT") (class "Default")
      (node (ref "C22") (pin "1") (pinfunction "1_1") (pintype "passive"))
      (node (ref "IC13") (pin "9") (pinfunction "PC15-OSC32_OUT_9") (pintype "bidirectional"))
      (node (ref "Q2") (pin "1") (pinfunction "OSC1_1") (pintype "passive"))
    )
    (net (code "38") (name "/PE0") (class "Default")
      (node (ref "IC13") (pin "141") (pinfunction "PE0_141") (pintype "bidirectional"))
      (node (ref "W1") (pin "3") (pinfunction "3_3") (pintype "bidirectional"))
    )
    (net (code "39") (name "/PE1") (class "Default")
      (node (ref "IC13") (pin "142") (pinfunction "PE1_142") (pintype "bidirectional"))
      (node (ref "W1") (pin "4") (pinfunction "4_4") (pintype "bidirectional"))
    )
    (net (code "40") (name "/PE2") (class "Default")
      (node (ref "IC13") (pin "1") (pinfunction "PE2_1") (pintype "bidirectional"))
      (node (ref "W1") (pin "6") (pinfunction "6_6") (pintype "bidirectional"))
    )
    (net (code "41") (name "/PE3") (class "Default")
      (node (ref "IC13") (pin "2") (pinfunction "PE3_2") (pintype "bidirectional"))
      (node (ref "W1") (pin "7") (pinfunction "7_7") (pintype "bidirectional"))
    )
    (net (code "42") (name "/PE4") (class "Default")
      (node (ref "IC13") (pin "3") (pinfunction "PE4_3") (pintype "bidirectional"))
      (node (ref "W1") (pin "8") (pinfunction "8_8") (pintype "bidirectional"))
    )
    (net (code "43") (name "/PE5") (class "Default")
      (node (ref "IC13") (pin "4") (pinfunction "PE5_4") (pintype "bidirectional"))
      (node (ref "W1") (pin "9") (pinfunction "9_9") (pintype "bidirectional"))
    )
    (net (code "44") (name "/PE6") (class "Default")
      (node (ref "IC13") (pin "5") (pinfunction "PE6_5") (pintype "bidirectional+no_connect"))
    )
    (net (code "45") (name "/PE7") (class "Default")
      (node (ref "IC13") (pin "58") (pinfunction "PE7_58") (pintype "bidirectional+no_connect"))
    )
    (net (code "46") (name "/PE10") (class "Default")
      (node (ref "IC13") (pin "63") (pinfunction "PE10_63") (pintype "bidirectional+no_connect"))
    )
    (net (code "47") (name "/PF12_ADCIN") (class "Default")
      (node (ref "IC13") (pin "50") (pinfunction "PF12_50") (pintype "bidirectional"))
      (node (ref "W1") (pin "2") (pinfunction "2_2") (pintype "bidirectional"))
    )
    (net (code "48") (name "/PF13_ADCIN") (class "Default")
      (node (ref "IC13") (pin "53") (pinfunction "PF13_53") (pintype "bidirectional"))
      (node (ref "W1") (pin "1") (pinfunction "1_1") (pintype "bidirectional"))
    )
    (net (code "49") (name "/PHY_NRST") (class "Default")
      (node (ref "IC13") (pin "129") (pinfunction "PG14_129") (pintype "bidirectional"))
    )
    (net (code "50") (name "/POE_PWR_SRC") (class "Default")
      (node (ref "IC13") (pin "37") (pinfunction "PA3_37") (pintype "bidirectional"))
    )
    (net (code "51") (name "/QSPI_BK1_CLK") (class "Default")
      (node (ref "IC13") (pin "22") (pinfunction "PF10_22") (pintype "bidirectional"))
      (node (ref "IC14") (pin "6") (pinfunction "CLK_6") (pintype "input"))
    )
    (net (code "52") (name "/QSPI_BK1_D0") (class "Default")
      (node (ref "IC13") (pin "20") (pinfunction "PF8_20") (pintype "bidirectional"))
      (node (ref "IC14") (pin "5") (pinfunction "DI(IO0)_5") (pintype "bidirectional"))
    )
    (net (code "53") (name "/QSPI_BK1_D1") (class "Default")
      (node (ref "IC13") (pin "21") (pinfunction "PF9_21") (pintype "bidirectional"))
      (node (ref "IC14") (pin "2") (pinfunction "DO(IO1)_2") (pintype "bidirectional"))
    )
    (net (code "54") (name "/QSPI_BK1_D2") (class "Default")
      (node (ref "IC13") (pin "19") (pinfunction "PF7_19") (pintype "bidirectional"))
      (node (ref "IC14") (pin "3") (pinfunction "~{WP}(IO2)_3") (pintype "bidirectional"))
    )
    (net (code "55") (name "/QSPI_BK1_D3") (class "Default")
      (node (ref "IC13") (pin "18") (pinfunction "PF6_18") (pintype "bidirectional"))
      (node (ref "IC14") (pin "7") (pinfunction "~{HOLD}_~{RST}(IO3)_7") (pintype "bidirectional"))
    )
    (net (code "56") (name "/QSPI_BK1_NSS") (class "Default")
      (node (ref "IC13") (pin "91") (pinfunction "PG6_91") (pintype "bidirectional"))
      (node (ref "IC14") (pin "1") (pinfunction "~{CS}_1") (pintype "input"))
      (node (ref "R76") (pin "1") (pinfunction "1_1") (pintype "passive"))
    )
    (net (code "57") (name "/RCC_MCO_1") (class "Default")
      (node (ref "B5") (pin "1") (pinfunction "1_1") (pintype "bidirectional"))
      (node (ref "IC13") (pin "100") (pinfunction "PA8_100") (pintype "bidirectional"))
    )
    (net (code "58") (name "/RMII_CRS_DV") (class "Default")
      (node (ref "IC13") (pin "43") (pinfunction "PA7_43") (pintype "bidirectional"))
    )
    (net (code "59") (name "/RMII_MDC") (class "Default")
      (node (ref "IC13") (pin "27") (pinfunction "PC1_27") (pintype "bidirectional"))
    )
    (net (code "60") (name "/RMII_MDIO") (class "Default")
      (node (ref "IC13") (pin "36") (pinfunction "PA2_36") (pintype "bidirectional"))
    )
    (net (code "61") (name "/RMII_REF_CLK") (class "Default")
      (node (ref "IC13") (pin "35") (pinfunction "PA1_35") (pintype "bidirectional"))
    )
    (net (code "62") (name "/RMII_RXD0") (class "Default")
      (node (ref "IC13") (pin "44") (pinfunction "PC4_44") (pintype "bidirectional"))
    )
    (net (code "63") (name "/RMII_RXD1") (class "Default")
      (node (ref "IC13") (pin "45") (pinfunction "PC5_45") (pintype "bidirectional"))
    )
    (net (code "64") (name "/RMII_TXD0") (class "Default")
      (node (ref "IC13") (pin "128") (pinfunction "PG13_128") (pintype "bidirectional"))
    )
    (net (code "65") (name "/RMII_TXD1") (class "Default")
      (node (ref "IC13") (pin "127") (pinfunction "PG12_127") (pintype "bidirectional"))
    )
    (net (code "66") (name "/RMII_TX_EN") (class "Default")
      (node (ref "IC13") (pin "126") (pinfunction "PG11_126") (pintype "bidirectional"))
    )
    (net (code "67") (name "/RSTn") (class "Default")
      (node (ref "D11") (pin "2") (pinfunction "A_2") (pintype "passive"))
      (node (ref "IC13") (pin "25") (pinfunction "~{RST}_25") (pintype "input"))
      (node (ref "J86") (pin "10") (pinfunction "10_10") (pintype "bidirectional"))
      (node (ref "R89") (pin "1") (pinfunction "1_1") (pintype "passive"))
    )
    (net (code "68") (name "/RXD") (class "Default")
      (node (ref "IC13") (pin "137") (pinfunction "PB7_137") (pintype "bidirectional"))
      (node (ref "R90") (pin "1") (pinfunction "1_1") (pintype "passive"))
    )
    (net (code "69") (name "/Rx") (class "Default")
      (node (ref "R90") (pin "2") (pinfunction "2_2") (pintype "passive"))
      (node (ref "W2") (pin "2") (pinfunction "2_2") (pintype "bidirectional"))
    )
    (net (code "70") (name "/SD_CK") (class "Default")
      (node (ref "D10") (pin "1") (pinfunction "I/O1_1") (pintype "bidirectional"))
      (node (ref "IC13") (pin "113") (pinfunction "PC12_113") (pintype "bidirectional"))
      (node (ref "J85") (pin "5") (pinfunction "CLK_5") (pintype "output"))
      (node (ref "R69") (pin "1") (pinfunction "1_1") (pintype "passive"))
    )
    (net (code "71") (name "/SD_CMD") (class "Default")
      (node (ref "D9") (pin "4") (pinfunction "I/O3_4") (pintype "bidirectional"))
      (node (ref "IC13") (pin "116") (pinfunction "PD2_116") (pintype "bidirectional"))
      (node (ref "J85") (pin "3") (pinfunction "CMD_3") (pintype "bidirectional"))
      (node (ref "R68") (pin "1") (pinfunction "1_1") (pintype "passive"))
    )
    (net (code "72") (name "/SD_D0") (class "Default")
      (node (ref "D10") (pin "4") (pinfunction "I/O3_4") (pintype "bidirectional"))
      (node (ref "IC13") (pin "98") (pinfunction "PC8_98") (pintype "bidirectional"))
      (node (ref "J85") (pin "7") (pinfunction "DAT0_7") (pintype "bidirectional"))
      (node (ref "R70") (pin "1") (pinfunction "1_1") (pintype "passive"))
    )
    (net (code "73") (name "/SD_D1") (class "Default")
      (node (ref "D10") (pin "6") (pinfunction "I/O4_6") (pintype "bidirectional"))
      (node (ref "IC13") (pin "99") (pinfunction "PC9_99") (pintype "bidirectional"))
      (node (ref "J85") (pin "8") (pinfunction "DAT1_8") (pintype "bidirectional"))
      (node (ref "R71") (pin "1") (pinfunction "1_1") (pintype "passive"))
    )
    (net (code "74") (name "/SD_D2") (class "Default")
      (node (ref "D9") (pin "1") (pinfunction "I/O1_1") (pintype "bidirectional"))
      (node (ref "IC13") (pin "111") (pinfunction "PC10_111") (pintype "bidirectional"))
      (node (ref "J85") (pin "1") (pinfunction "DAT2_1") (pintype "bidirectional"))
      (node (ref "R66") (pin "1") (pinfunction "1_1") (pintype "passive"))
    )
    (net (code "75") (name "/SD_D3") (class "Default")
      (node (ref "D9") (pin "3") (pinfunction "I/O2_3") (pintype "bidirectional"))
      (node (ref "IC13") (pin "112") (pinfunction "PC11_112") (pintype "bidirectional"))
      (node (ref "J85") (pin "2") (pinfunction "DAT3_2") (pintype "bidirectional"))
      (node (ref "R67") (pin "1") (pinfunction "1_1") (pintype "passive"))
    )
    (net (code "76") (name "/SD_SW") (class "Default")
      (node (ref "D9") (pin "6") (pinfunction "I/O4_6") (pintype "bidirectional"))
      (node (ref "IC13") (pin "117") (pinfunction "PD3_117") (pintype "bidirectional"))
      (node (ref "J85") (pin "12") (pinfunction "DETSW_12") (pintype "passive"))
      (node (ref "R72") (pin "1") (pinfunction "1_1") (pintype "passive"))
    )
    (net (code "77") (name "/SPI1_MISO") (class "Default")
      (node (ref "IC13") (pin "42") (pinfunction "PA6_42") (pintype "bidirectional"))
    )
    (net (code "78") (name "/SPI1_MOSI") (class "Default")
      (node (ref "IC13") (pin "135") (pinfunction "PB5_135") (pintype "bidirectional"))
    )
    (net (code "79") (name "/SPI1_NSS") (class "Default")
      (node (ref "IC13") (pin "40") (pinfunction "PA4_40") (pintype "bidirectional"))
    )
    (net (code "80") (name "/SPI1_SCK") (class "Default")
      (node (ref "IC13") (pin "41") (pinfunction "PA5_41") (pintype "bidirectional"))
    )
    (net (code "81") (name "/SPI4_CLK") (class "Default")
      (node (ref "IC13") (pin "65") (pinfunction "PE12_65") (pintype "bidirectional"))
    )
    (net (code "82") (name "/SPI4_MISO") (class "Default")
      (node (ref "IC13") (pin "66") (pinfunction "PE13_66") (pintype "bidirectional"))
    )
    (net (code "83") (name "/SPI4_MOSI") (class "Default")
      (node (ref "IC13") (pin "67") (pinfunction "PE14_67") (pintype "bidirectional"))
    )
    (net (code "84") (name "/SPI4_NSS") (class "Default")
      (node (ref "IC13") (pin "64") (pinfunction "PE11_64") (pintype "bidirectional"))
    )
    (net (code "85") (name "/SWCLK") (class "Default")
      (node (ref "D8") (pin "1") (pinfunction "I/O1_1") (pintype "bidirectional"))
      (node (ref "IC13") (pin "109") (pinfunction "PA14_109") (pintype "bidirectional"))
      (node (ref "J86") (pin "4") (pinfunction "4_4") (pintype "bidirectional"))
    )
    (net (code "86") (name "/SWDIO") (class "Default")
      (node (ref "D8") (pin "3") (pinfunction "I/O2_3") (pintype "bidirectional"))
      (node (ref "IC13") (pin "105") (pinfunction "PA13_105") (pintype "bidirectional"))
      (node (ref "J86") (pin "2") (pinfunction "2_2") (pintype "bidirectional"))
    )
    (net (code "87") (name "/TDI") (class "Default")
      (node (ref "D8") (pin "6") (pinfunction "I/O4_6") (pintype "bidirectional"))
      (node (ref "IC13") (pin "110") (pinfunction "PA15_110") (pintype "bidirectional"))
      (node (ref "J86") (pin "8") (pinfunction "8_8") (pintype "bidirectional"))
      (node (ref "R77") (pin "1") (pinfunction "1_1") (pintype "passive"))
    )
    (net (code "88") (name "/TDO") (class "Default")
      (node (ref "D8") (pin "4") (pinfunction "I/O3_4") (pintype "bidirectional"))
      (node (ref "IC13") (pin "133") (pinfunction "PB3_133") (pintype "bidirectional"))
      (node (ref "J86") (pin "6") (pinfunction "6_6") (pintype "bidirectional"))
    )
    (net (code "89") (name "/TXD") (class "Default")
      (node (ref "IC13") (pin "136") (pinfunction "PB6_136") (pintype "bidirectional"))
      (node (ref "R91") (pin "1") (pinfunction "1_1") (pintype "passive"))
    )
    (net (code "90") (name "/Tx") (class "Default")
      (node (ref "R91") (pin "2") (pinfunction "2_2") (pintype "passive"))
      (node (ref "W2") (pin "3") (pinfunction "3_3") (pintype "bidirectional"))
    )
    (net (code "91") (name "/USB_ID") (class "Default")
      (node (ref "IC13") (pin "102") (pinfunction "PA10_102") (pintype "bidirectional"))
    )
    (net (code "92") (name "/USB_N") (class "Default")
      (node (ref "IC13") (pin "103") (pinfunction "PA11_103") (pintype "bidirectional"))
    )
    (net (code "93") (name "/USB_P") (class "Default")
      (node (ref "IC13") (pin "104") (pinfunction "PA12_104") (pintype "bidirectional"))
    )
    (net (code "94") (name "/USB_VBUS") (class "Default")
      (node (ref "IC13") (pin "101") (pinfunction "PA9_101") (pintype "bidirectional"))
    )
    (net (code "95") (name "/U_meas_P3V3") (class "Default")
      (node (ref "C21") (pin "2") (pinfunction "2_2") (pintype "passive"))
      (node (ref "IC13") (pin "28") (pinfunction "PC2_C_28") (pintype "bidirectional"))
      (node (ref "R63") (pin "1") (pinfunction "1_1") (pintype "passive"))
      (node (ref "R65") (pin "2") (pinfunction "2_2") (pintype "passive"))
    )
    (net (code "96") (name "/U_meas_P12V0") (class "Default")
      (node (ref "C18") (pin "2") (pinfunction "2_2") (pintype "passive"))
      (node (ref "IC13") (pin "26") (pinfunction "PC0_26") (pintype "bidirectional"))
      (node (ref "R57") (pin "1") (pinfunction "1_1") (pintype "passive"))
      (node (ref "R58") (pin "2") (pinfunction "2_2") (pintype "passive"))
    )
    (net (code "97") (name "/VBAT") (class "Default")
      (node (ref "BATH1") (pin "1") (pinfunction "PLUS_1") (pintype "power_in"))
      (node (ref "C32") (pin "2") (pinfunction "2_2") (pintype "passive"))
      (node (ref "IC13") (pin "6") (pinfunction "VBAT_6") (pintype "power_in"))
    )
    (net (code "98") (name "/VDDA") (class "Default")
      (node (ref "C28") (pin "2") (pinfunction "2_2") (pintype "passive"))
      (node (ref "C29") (pin "2") (pinfunction "2_2") (pintype "passive"))
      (node (ref "IC13") (pin "33") (pinfunction "VDDA_33") (pintype "power_in"))
      (node (ref "L1") (pin "2") (pinfunction "2_2") (pintype "passive"))
    )
    (net (code "99") (name "/VREF+") (class "Default")
      (node (ref "C33") (pin "2") (pinfunction "2_2") (pintype "passive"))
      (node (ref "C35") (pin "2") (pinfunction "2_2") (pintype "passive"))
      (node (ref "IC13") (pin "32") (pinfunction "VREF+_32") (pintype "power_in"))
      (node (ref "L2") (pin "1") (pinfunction "1_1") (pintype "passive"))
    )
    (net (code "100") (name "/XTAL_IN") (class "Default")
      (node (ref "C19") (pin "2") (pinfunction "2_2") (pintype "passive"))
      (node (ref "IC13") (pin "23") (pinfunction "PH0-OSC_IN_23") (pintype "bidirectional"))
      (node (ref "Q1") (pin "1") (pinfunction "Crystal_1") (pintype "passive"))
    )
    (net (code "103") (name "GND") (class "Default")
      (node (ref "BATH1") (pin "2") (pinfunction "MINUS_2") (pintype "power_in"))
      (node (ref "C18") (pin "1") (pinfunction "1_1") (pintype "passive"))
      (node (ref "C19") (pin "1") (pinfunction "1_1") (pintype "passive"))
      (node (ref "C20") (pin "2") (pinfunction "2_2") (pintype "passive"))
      (node (ref "C21") (pin "1") (pinfunction "1_1") (pintype "passive"))
      (node (ref "C22") (pin "2") (pinfunction "2_2") (pintype "passive"))
      (node (ref "C23") (pin "2") (pinfunction "2_2") (pintype "passive"))
      (node (ref "C25") (pin "1") (pinfunction "1_1") (pintype "passive"))
      (node (ref "C26") (pin "1") (pinfunction "1_1") (pintype "passive"))
      (node (ref "C27") (pin "1") (pinfunction "1_1") (pintype "passive"))
      (node (ref "C28") (pin "1") (pinfunction "1_1") (pintype "passive"))
      (node (ref "C29") (pin "1") (pinfunction "1_1") (pintype "passive"))
      (node (ref "C30") (pin "1") (pinfunction "1_1") (pintype "passive"))
      (node (ref "C31") (pin "1") (pinfunction "1_1") (pintype "passive"))
      (node (ref "C32") (pin "1") (pinfunction "1_1") (pintype "passive"))
      (node (ref "C33") (pin "1") (pinfunction "1_1") (pintype "passive"))
      (node (ref "C34") (pin "1") (pinfunction "1_1") (pintype "passive"))
      (node (ref "C35") (pin "1") (pinfunction "1_1") (pintype "passive"))
      (node (ref "C36") (pin "1") (pinfunction "1_1") (pintype "passive"))
      (node (ref "C37") (pin "1") (pinfunction "1_1") (pintype "passive"))
      (node (ref "C38") (pin "1") (pinfunction "1_1") (pintype "passive"))
      (node (ref "C39") (pin "1") (pinfunction "1_1") (pintype "passive"))
      (node (ref "C40") (pin "1") (pinfunction "1_1") (pintype "passive"))
      (node (ref "C41") (pin "1") (pinfunction "1_1") (pintype "passive"))
      (node (ref "C42") (pin "1") (pinfunction "1_1") (pintype "passive"))
      (node (ref "C43") (pin "1") (pinfunction "1_1") (pintype "passive"))
      (node (ref "C44") (pin "1") (pinfunction "1_1") (pintype "passive"))
      (node (ref "C45") (pin "1") (pinfunction "1_1") (pintype "passive"))
      (node (ref "C46") (pin "1") (pinfunction "1_1") (pintype "passive"))
      (node (ref "C47") (pin "1") (pinfunction "1_1") (pintype "passive"))
      (node (ref "C48") (pin "1") (pinfunction "1_1") (pintype "passive"))
      (node (ref "C49") (pin "1") (pinfunction "1_1") (pintype "passive"))
      (node (ref "D10") (pin "2") (pinfunction "GND_2") (pintype "power_in"))
      (node (ref "D8") (pin "2") (pinfunction "GND_2") (pintype "power_in"))
      (node (ref "D9") (pin "2") (pinfunction "GND_2") (pintype "power_in"))
      (node (ref "IC13") (pin "107") (pinfunction "VSS_107") (pintype "power_in"))
      (node (ref "IC13") (pin "120") (pinfunction "VSS_120") (pintype "power_in"))
      (node (ref "IC13") (pin "130") (pinfunction "VSS_130") (pintype "power_in"))
      (node (ref "IC13") (pin "16") (pinfunction "VSS_16") (pintype "power_in"))
      (node (ref "IC13") (pin "31") (pinfunction "VSSA_31") (pintype "power_in"))
      (node (ref "IC13") (pin "38") (pinfunction "VSS_38") (pintype "power_in"))
      (node (ref "IC13") (pin "51") (pinfunction "VSS_51") (pintype "power_in"))
      (node (ref "IC13") (pin "61") (pinfunction "VSS_61") (pintype "power_in"))
      (node (ref "IC13") (pin "83") (pinfunction "VSS_83") (pintype "power_in"))
      (node (ref "IC13") (pin "94") (pinfunction "VSS_94") (pintype "power_in"))
      (node (ref "IC14") (pin "4") (pinfunction "GND_4") (pintype "power_in"))
      (node (ref "IC15") (pin "1") (pinfunction "VSS_1") (pintype "power_in"))
      (node (ref "J85") (pin "10") (pinfunction "10_10") (pintype "passive"))
      (node (ref "J85") (pin "11") (pinfunction "11_11") (pintype "passive"))
      (node (ref "J85") (pin "13") (pinfunction "13_13") (pintype "passive"))
      (node (ref "J85") (pin "14") (pinfunction "DETLEV_14") (pintype "passive"))
      (node (ref "J85") (pin "6") (pinfunction "VSS_6") (pintype "power_in"))
      (node (ref "J85") (pin "9") (pinfunction "9_9") (pintype "passive"))
      (node (ref "J86") (pin "3") (pinfunction "3_3") (pintype "bidirectional"))
      (node (ref "J86") (pin "5") (pinfunction "5_5") (pintype "bidirectional"))
      (node (ref "LD4") (pin "1") (pinfunction "C_1") (pintype "passive"))
      (node (ref "LD4") (pin "3") (pinfunction "C_3") (pintype "passive"))
      (node (ref "LD4") (pin "5") (pinfunction "C_5") (pintype "passive"))
      (node (ref "LD4") (pin "7") (pinfunction "C_7") (pintype "passive"))
      (node (ref "LD5") (pin "1") (pinfunction "C_1") (pintype "passive"))
      (node (ref "LD5") (pin "3") (pinfunction "C_3") (pintype "passive"))
      (node (ref "LD5") (pin "5") (pinfunction "C_5") (pintype "passive"))
      (node (ref "LD5") (pin "7") (pinfunction "C_7") (pintype "passive"))
      (node (ref "Q1") (pin "2") (pinfunction "GND&Lid_2") (pintype "passive"))
      (node (ref "Q1") (pin "4") (pinfunction "GND&Lid_4") (pintype "passive"))
      (node (ref "R56") (pin "1") (pinfunction "1_1") (pintype "passive"))
      (node (ref "R58") (pin "1") (pinfunction "1_1") (pintype "passive"))
      (node (ref "R59") (pin "2") (pinfunction "2_2") (pintype "passive"))
      (node (ref "R60") (pin "2") (pinfunction "2_2") (pintype "passive"))
      (node (ref "R61") (pin "2") (pinfunction "2_2") (pintype "passive"))
      (node (ref "R62") (pin "2") (pinfunction "2_2") (pintype "passive"))
      (node (ref "R64") (pin "2") (pinfunction "2_2") (pintype "passive"))
      (node (ref "R65") (pin "1") (pinfunction "1_1") (pintype "passive"))
      (node (ref "W1") (pin "5") (pinfunction "5_5") (pintype "bidirectional"))
      (node (ref "W2") (pin "4") (pinfunction "4_4") (pintype "bidirectional"))
    )
    (net (code "104") (name "Net-(C30-Pad2)") (class "Default")
      (node (ref "C30") (pin "2") (pinfunction "2_2") (pintype "passive"))
      (node (ref "IC13") (pin "71") (pinfunction "VCAP_71") (pintype "power_in"))
    )
    (net (code "105") (name "Net-(C31-Pad2)") (class "Default")
      (node (ref "C31") (pin "2") (pinfunction "2_2") (pintype "passive"))
      (node (ref "IC13") (pin "106") (pinfunction "VCAP_106") (pintype "power_in"))
    )
    (net (code "106") (name "Net-(C34-Pad2)") (class "Default")
      (node (ref "C34") (pin "2") (pinfunction "2_2") (pintype "passive"))
      (node (ref "C36") (pin "2") (pinfunction "2_2") (pintype "passive"))
      (node (ref "L2") (pin "2") (pinfunction "2_2") (pintype "passive"))
      (node (ref "R86") (pin "1") (pinfunction "1_1") (pintype "passive"))
    )
    (net (code "107") (name "Net-(IC13B-PB2)") (class "Default")
      (node (ref "IC13") (pin "48") (pinfunction "PB2_48") (pintype "bidirectional"))
      (node (ref "R64") (pin "1") (pinfunction "1_1") (pintype "passive"))
    )
    (net (code "108") (name "Net-(IC13C-PH1-OSC_OUT)") (class "Default")
      (node (ref "C20") (pin "1") (pinfunction "1_1") (pintype "passive"))
      (node (ref "IC13") (pin "24") (pinfunction "PH1-OSC_OUT_24") (pintype "bidirectional"))
      (node (ref "Q1") (pin "3") (pinfunction "Crystal_3") (pintype "passive"))
    )
    (net (code "109") (name "Net-(LD4A-A)") (class "Default")
      (node (ref "LD4") (pin "2") (pinfunction "A_2") (pintype "passive"))
      (node (ref "R78") (pin "2") (pinfunction "2_2") (pintype "passive"))
    )
    (net (code "110") (name "Net-(LD4B-A)") (class "Default")
      (node (ref "LD4") (pin "4") (pinfunction "A_4") (pintype "passive"))
      (node (ref "R81") (pin "2") (pinfunction "2_2") (pintype "passive"))
    )
    (net (code "111") (name "Net-(LD4C-A)") (class "Default")
      (node (ref "LD4") (pin "6") (pinfunction "A_6") (pintype "passive"))
      (node (ref "R82") (pin "2") (pinfunction "2_2") (pintype "passive"))
    )
    (net (code "112") (name "Net-(LD4D-A)") (class "Default")
      (node (ref "LD4") (pin "8") (pinfunction "A_8") (pintype "passive"))
      (node (ref "R83") (pin "2") (pinfunction "2_2") (pintype "passive"))
    )
    (net (code "113") (name "Net-(LD5A-A)") (class "Default")
      (node (ref "LD5") (pin "2") (pinfunction "A_2") (pintype "passive"))
      (node (ref "R84") (pin "2") (pinfunction "2_2") (pintype "passive"))
    )
    (net (code "114") (name "Net-(LD5B-A)") (class "Default")
      (node (ref "LD5") (pin "4") (pinfunction "A_4") (pintype "passive"))
      (node (ref "R85") (pin "2") (pinfunction "2_2") (pintype "passive"))
    )
    (net (code "115") (name "Net-(LD5C-A)") (class "Default")
      (node (ref "LD5") (pin "6") (pinfunction "A_6") (pintype "passive"))
      (node (ref "R87") (pin "2") (pinfunction "2_2") (pintype "passive"))
    )
    (net (code "116") (name "Net-(LD5D-A)") (class "Default")
      (node (ref "LD5") (pin "8") (pinfunction "A_8") (pintype "passive"))
      (node (ref "R88") (pin "2") (pinfunction "2_2") (pintype "passive"))
    )
    (net (code "117") (name "P3V3") (class "Default")
      (node (ref "C25") (pin "2") (pinfunction "2_2") (pintype "passive"))
      (node (ref "C26") (pin "2") (pinfunction "2_2") (pintype "passive"))
      (node (ref "C27") (pin "2") (pinfunction "2_2") (pintype "passive"))
      (node (ref "C37") (pin "2") (pinfunction "2_2") (pintype "passive"))
      (node (ref "C38") (pin "2") (pinfunction "2_2") (pintype "passive"))
      (node (ref "C39") (pin "2") (pinfunction "2_2") (pintype "passive"))
      (node (ref "C40") (pin "2") (pinfunction "2_2") (pintype "passive"))
      (node (ref "C41") (pin "2") (pinfunction "2_2") (pintype "passive"))
      (node (ref "C42") (pin "2") (pinfunction "2_2") (pintype "passive"))
      (node (ref "C43") (pin "2") (pinfunction "2_2") (pintype "passive"))
      (node (ref "C44") (pin "2") (pinfunction "2_2") (pintype "passive"))
      (node (ref "C45") (pin "2") (pinfunction "2_2") (pintype "passive"))
      (node (ref "C46") (pin "2") (pinfunction "2_2") (pintype "passive"))
      (node (ref "C47") (pin "2") (pinfunction "2_2") (pintype "passive"))
      (node (ref "C48") (pin "2") (pinfunction "2_2") (pintype "passive"))
      (node (ref "C49") (pin "2") (pinfunction "2_2") (pintype "passive"))
      (node (ref "D10") (pin "5") (pinfunction "VBUS_5") (pintype "power_in"))
      (node (ref "D8") (pin "5") (pinfunction "VBUS_5") (pintype "power_in"))
      (node (ref "D9") (pin "5") (pinfunction "VBUS_5") (pintype "power_in"))
      (node (ref "IC13") (pin "108") (pinfunction "VDD_108") (pintype "power_in"))
      (node (ref "IC13") (pin "121") (pinfunction "VDD_121") (pintype "power_in"))
      (node (ref "IC13") (pin "131") (pinfunction "VDD_131") (pintype "power_in"))
      (node (ref "IC13") (pin "143") (pinfunction "PDR_ON_143") (pintype "power_in"))
      (node (ref "IC13") (pin "144") (pinfunction "VDD_144") (pintype "power_in"))
      (node (ref "IC13") (pin "17") (pinfunction "VDD_17") (pintype "power_in"))
      (node (ref "IC13") (pin "30") (pinfunction "VDD_30") (pintype "power_in"))
      (node (ref "IC13") (pin "39") (pinfunction "VDD_39") (pintype "power_in"))
      (node (ref "IC13") (pin "52") (pinfunction "VDD_52") (pintype "power_in"))
      (node (ref "IC13") (pin "62") (pinfunction "VDD_62") (pintype "power_in"))
      (node (ref "IC13") (pin "72") (pinfunction "VDD_72") (pintype "power_in"))
      (node (ref "IC13") (pin "84") (pinfunction "VDD_84") (pintype "power_in"))
      (node (ref "IC13") (pin "95") (pinfunction "VDD33USB_95") (pintype "power_in"))
      (node (ref "IC14") (pin "8") (pinfunction "VCC_8") (pintype "power_in"))
      (node (ref "IC15") (pin "3") (pinfunction "VCC_3") (pintype "power_in"))
      (node (ref "J85") (pin "4") (pinfunction "VDD_4") (pintype "power_in"))
      (node (ref "J86") (pin "1") (pinfunction "1_1") (pintype "bidirectional"))
      (node (ref "JP1") (pin "1") (pinfunction "E1_1") (pintype "passive"))
      (node (ref "L1") (pin "1") (pinfunction "1_1") (pintype "passive"))
      (node (ref "R63") (pin "2") (pinfunction "2_2") (pintype "passive"))
      (node (ref "R66") (pin "2") (pinfunction "2_2") (pintype "passive"))
      (node (ref "R67") (pin "2") (pinfunction "2_2") (pintype "passive"))
      (node (ref "R68") (pin "2") (pinfunction "2_2") (pintype "passive"))
      (node (ref "R69") (pin "2") (pinfunction "2_2") (pintype "passive"))
      (node (ref "R70") (pin "2") (pinfunction "2_2") (pintype "passive"))
      (node (ref "R71") (pin "2") (pinfunction "2_2") (pintype "passive"))
      (node (ref "R72") (pin "2") (pinfunction "2_2") (pintype "passive"))
      (node (ref "R76") (pin "2") (pinfunction "2_2") (pintype "passive"))
      (node (ref "R77") (pin "2") (pinfunction "2_2") (pintype "passive"))
      (node (ref "R79") (pin "1") (pinfunction "1_1") (pintype "passive"))
      (node (ref "R80") (pin "1") (pinfunction "1_1") (pintype "passive"))
      (node (ref "R86") (pin "2") (pinfunction "2_2") (pintype "passive"))
      (node (ref "R89") (pin "2") (pinfunction "2_2") (pintype "passive"))
      (node (ref "W1") (pin "10") (pinfunction "10_10") (pintype "bidirectional"))
      (node (ref "W2") (pin "1") (pinfunction "1_1") (pintype "bidirectional"))
    )
    (net (code "118") (name "VIN") (class "Default")
      (node (ref "R57") (pin "2") (pinfunction "2_2") (pintype "passive"))
    )
    (net (code "119") (name "unconnected-(D10-I{slash}O2-Pad3)") (class "Default")
      (node (ref "D10") (pin "3") (pinfunction "I/O2_3") (pintype "bidirectional"))
    )
    (net (code "120") (name "unconnected-(IC13B-PB11-Pad70)") (class "Default")
      (node (ref "IC13") (pin "70") (pinfunction "PB11_70") (pintype "bidirectional+no_connect"))
    )
    (net (code "121") (name "unconnected-(IC13B-PB13-Pad74)") (class "Default")
      (node (ref "IC13") (pin "74") (pinfunction "PB13_74") (pintype "bidirectional+no_connect"))
    )
    (net (code "122") (name "unconnected-(IC13B-PC3_C-Pad29)") (class "Default")
      (node (ref "IC13") (pin "29") (pinfunction "PC3_C_29") (pintype "bidirectional+no_connect"))
    )
    (net (code "123") (name "unconnected-(IC13B-PC6-Pad96)") (class "Default")
      (node (ref "IC13") (pin "96") (pinfunction "PC6_96") (pintype "bidirectional+no_connect"))
    )
    (net (code "124") (name "unconnected-(IC13B-PC7-Pad97)") (class "Default")
      (node (ref "IC13") (pin "97") (pinfunction "PC7_97") (pintype "bidirectional+no_connect"))
    )
    (net (code "125") (name "unconnected-(IC13B-PC13-Pad7)") (class "Default")
      (node (ref "IC13") (pin "7") (pinfunction "PC13_7") (pintype "bidirectional+no_connect"))
    )
    (net (code "126") (name "unconnected-(IC13B-PG2-Pad87)") (class "Default")
      (node (ref "IC13") (pin "87") (pinfunction "PG2_87") (pintype "bidirectional+no_connect"))
    )
    (net (code "127") (name "unconnected-(IC13B-PG3-Pad88)") (class "Default")
      (node (ref "IC13") (pin "88") (pinfunction "PG3_88") (pintype "bidirectional+no_connect"))
    )
    (net (code "128") (name "unconnected-(IC13B-PG4-Pad89)") (class "Default")
      (node (ref "IC13") (pin "89") (pinfunction "PG4_89") (pintype "bidirectional+no_connect"))
    )
    (net (code "129") (name "unconnected-(IC13B-PG5-Pad90)") (class "Default")
      (node (ref "IC13") (pin "90") (pinfunction "PG5_90") (pintype "bidirectional+no_connect"))
    )
    (net (code "130") (name "unconnected-(IC13B-PG7-Pad92)") (class "Default")
      (node (ref "IC13") (pin "92") (pinfunction "PG7_92") (pintype "bidirectional+no_connect"))
    )
    (net (code "131") (name "unconnected-(IC13B-PG8-Pad93)") (class "Default")
      (node (ref "IC13") (pin "93") (pinfunction "PG8_93") (pintype "bidirectional+no_connect"))
    )
    (net (code "132") (name "unconnected-(IC13B-PG9-Pad124)") (class "Default")
      (node (ref "IC13") (pin "124") (pinfunction "PG9_124") (pintype "bidirectional+no_connect"))
    )
    (net (code "133") (name "unconnected-(IC13B-PG10-Pad125)") (class "Default")
      (node (ref "IC13") (pin "125") (pinfunction "PG10_125") (pintype "bidirectional+no_connect"))
    )
    (net (code "134") (name "unconnected-(IC13B-PG15-Pad132)") (class "Default")
      (node (ref "IC13") (pin "132") (pinfunction "PG15_132") (pintype "bidirectional"))
    )
    (net (code "135") (name "unconnected-(IC13C-PA0-Pad34)") (class "Default")
      (node (ref "IC13") (pin "34") (pinfunction "PA0_34") (pintype "bidirectional"))
    )
    (net (code "136") (name "unconnected-(IC13C-PD4-Pad118)") (class "Default")
      (node (ref "IC13") (pin "118") (pinfunction "PD4_118") (pintype "bidirectional+no_connect"))
    )
    (net (code "137") (name "unconnected-(IC13C-PD5-Pad119)") (class "Default")
      (node (ref "IC13") (pin "119") (pinfunction "PD5_119") (pintype "bidirectional+no_connect"))
    )
    (net (code "138") (name "unconnected-(IC13C-PD6-Pad122)") (class "Default")
      (node (ref "IC13") (pin "122") (pinfunction "PD6_122") (pintype "bidirectional+no_connect"))
    )
    (net (code "139") (name "unconnected-(IC13C-PD7-Pad123)") (class "Default")
      (node (ref "IC13") (pin "123") (pinfunction "PD7_123") (pintype "bidirectional+no_connect"))
    )
    (net (code "140") (name "unconnected-(IC13C-PF11-Pad49)") (class "Default")
      (node (ref "IC13") (pin "49") (pinfunction "PF11_49") (pintype "bidirectional"))
    )
    (net (code "141") (name "unconnected-(J86-Pad7)") (class "Default")
      (node (ref "J86") (pin "7") (pinfunction "7_7") (pintype "bidirectional"))
    )
    (net (code "142") (name "unconnected-(J86-Pad9)") (class "Default")
      (node (ref "J86") (pin "9") (pinfunction "9_9") (pintype "bidirectional"))
    )
  )
)
